# blinker-with-leds.net
KiCad netlist of a schematic drawn in EAGLE
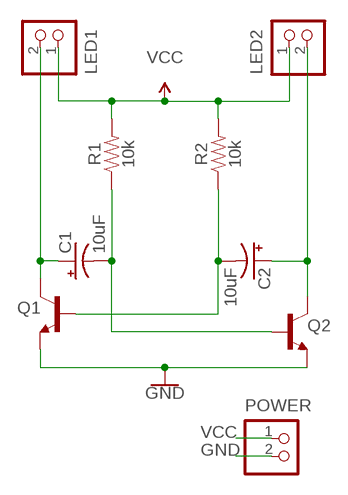
[diagram p0: schematic, sheet 1]

(export (version "E")
  (design (tool "Eeschema 10.0.6"))
  (components
    (comp (ref "C1")
      (value "10uF")
      (footprint "eagle-import:CPOL-RADIAL-2.5MM-5MM")
      (libsource (lib "eagle-import") (part "10UF-POLAR-RADIAL-2.5MM-25V-20%"))
    )
    (comp (ref "C2")
      (value "10uF")
      (footprint "eagle-import:CPOL-RADIAL-2.5MM-5MM")
      (libsource (lib "eagle-import") (part "10UF-POLAR-RADIAL-2.5MM-25V-20%"))
    )
    (comp (ref "LED1")
      (value "B2B-XH-A")
      (footprint "eagle-import:B2B-XH-A")
      (libsource (lib "eagle-import") (part "B2B-XH-A"))
    )
    (comp (ref "LED2")
      (value "B2B-XH-A")
      (footprint "eagle-import:B2B-XH-A")
      (libsource (lib "eagle-import") (part "B2B-XH-A"))
    )
    (comp (ref "POWER")
      (value "B2B-XH-A")
      (footprint "eagle-import:B2B-XH-A")
      (libsource (lib "eagle-import") (part "B2B-XH-A"))
    )
    (comp (ref "Q1")
      (value "600mA/40V")
      (footprint "eagle-import:TO-92")
      (libsource (lib "eagle-import") (part "TRANS_NPN-P2N2222A"))
    )
    (comp (ref "Q2")
      (value "600mA/40V")
      (footprint "eagle-import:TO-92")
      (libsource (lib "eagle-import") (part "TRANS_NPN-P2N2222A"))
    )
    (comp (ref "R1")
      (value "10k")
      (footprint "eagle-import:AXIAL-0.3")
      (libsource (lib "eagle-import") (part "10KOHM-HORIZ-1/4W-1%"))
    )
    (comp (ref "R2")
      (value "10k")
      (footprint "eagle-import:AXIAL-0.3")
      (libsource (lib "eagle-import") (part "10KOHM-HORIZ-1/4W-1%"))
    )
  )
  (nets
    (net (code "1") (name "GND") (class "Default")
      (node (ref "POWER") (pin "2") (pinfunction "2_2") (pintype "passive"))
      (node (ref "Q1") (pin "3") (pinfunction "E_3") (pintype "passive"))
      (node (ref "Q2") (pin "3") (pinfunction "E_3") (pintype "passive"))
    )
    (net (code "2") (name "Net-(C1-+)") (class "Default")
      (node (ref "C1") (pin "1") (pinfunction "+_1") (pintype "passive"))
      (node (ref "LED1") (pin "2") (pinfunction "2_2") (pintype "passive"))
      (node (ref "Q1") (pin "1") (pinfunction "C_1") (pintype "passive"))
    )
    (net (code "3") (name "Net-(C1--)") (class "Default")
      (node (ref "C1") (pin "2") (pinfunction "-_2") (pintype "passive"))
      (node (ref "Q2") (pin "2") (pinfunction "B_2") (pintype "passive"))
      (node (ref "R1") (pin "P$1") (pinfunction "1_P$1") (pintype "passive"))
    )
    (net (code "4") (name "Net-(C2-+)") (class "Default")
      (node (ref "C2") (pin "1") (pinfunction "+_1") (pintype "passive"))
      (node (ref "LED2") (pin "2") (pinfunction "2_2") (pintype "passive"))
      (node (ref "Q2") (pin "1") (pinfunction "C_1") (pintype "passive"))
    )
    (net (code "5") (name "Net-(C2--)") (class "Default")
      (node (ref "C2") (pin "2") (pinfunction "-_2") (pintype "passive"))
      (node (ref "Q1") (pin "2") (pinfunction "B_2") (pintype "passive"))
      (node (ref "R2") (pin "P$1") (pinfunction "1_P$1") (pintype "passive"))
    )
    (net (code "6") (name "VCC") (class "Default")
      (node (ref "LED1") (pin "1") (pinfunction "1_1") (pintype "passive"))
      (node (ref "LED2") (pin "1") (pinfunction "1_1") (pintype "passive"))
      (node (ref "POWER") (pin "1") (pinfunction "1_1") (pintype "passive"))
      (node (ref "R1") (pin "P$2") (pinfunction "2_P$2") (pintype "passive"))
      (node (ref "R2") (pin "P$2") (pinfunction "2_P$2") (pintype "passive"))
    )
  )
)
